# brashmi.net
KiCad netlist of a schematic drawn in EasyEDA
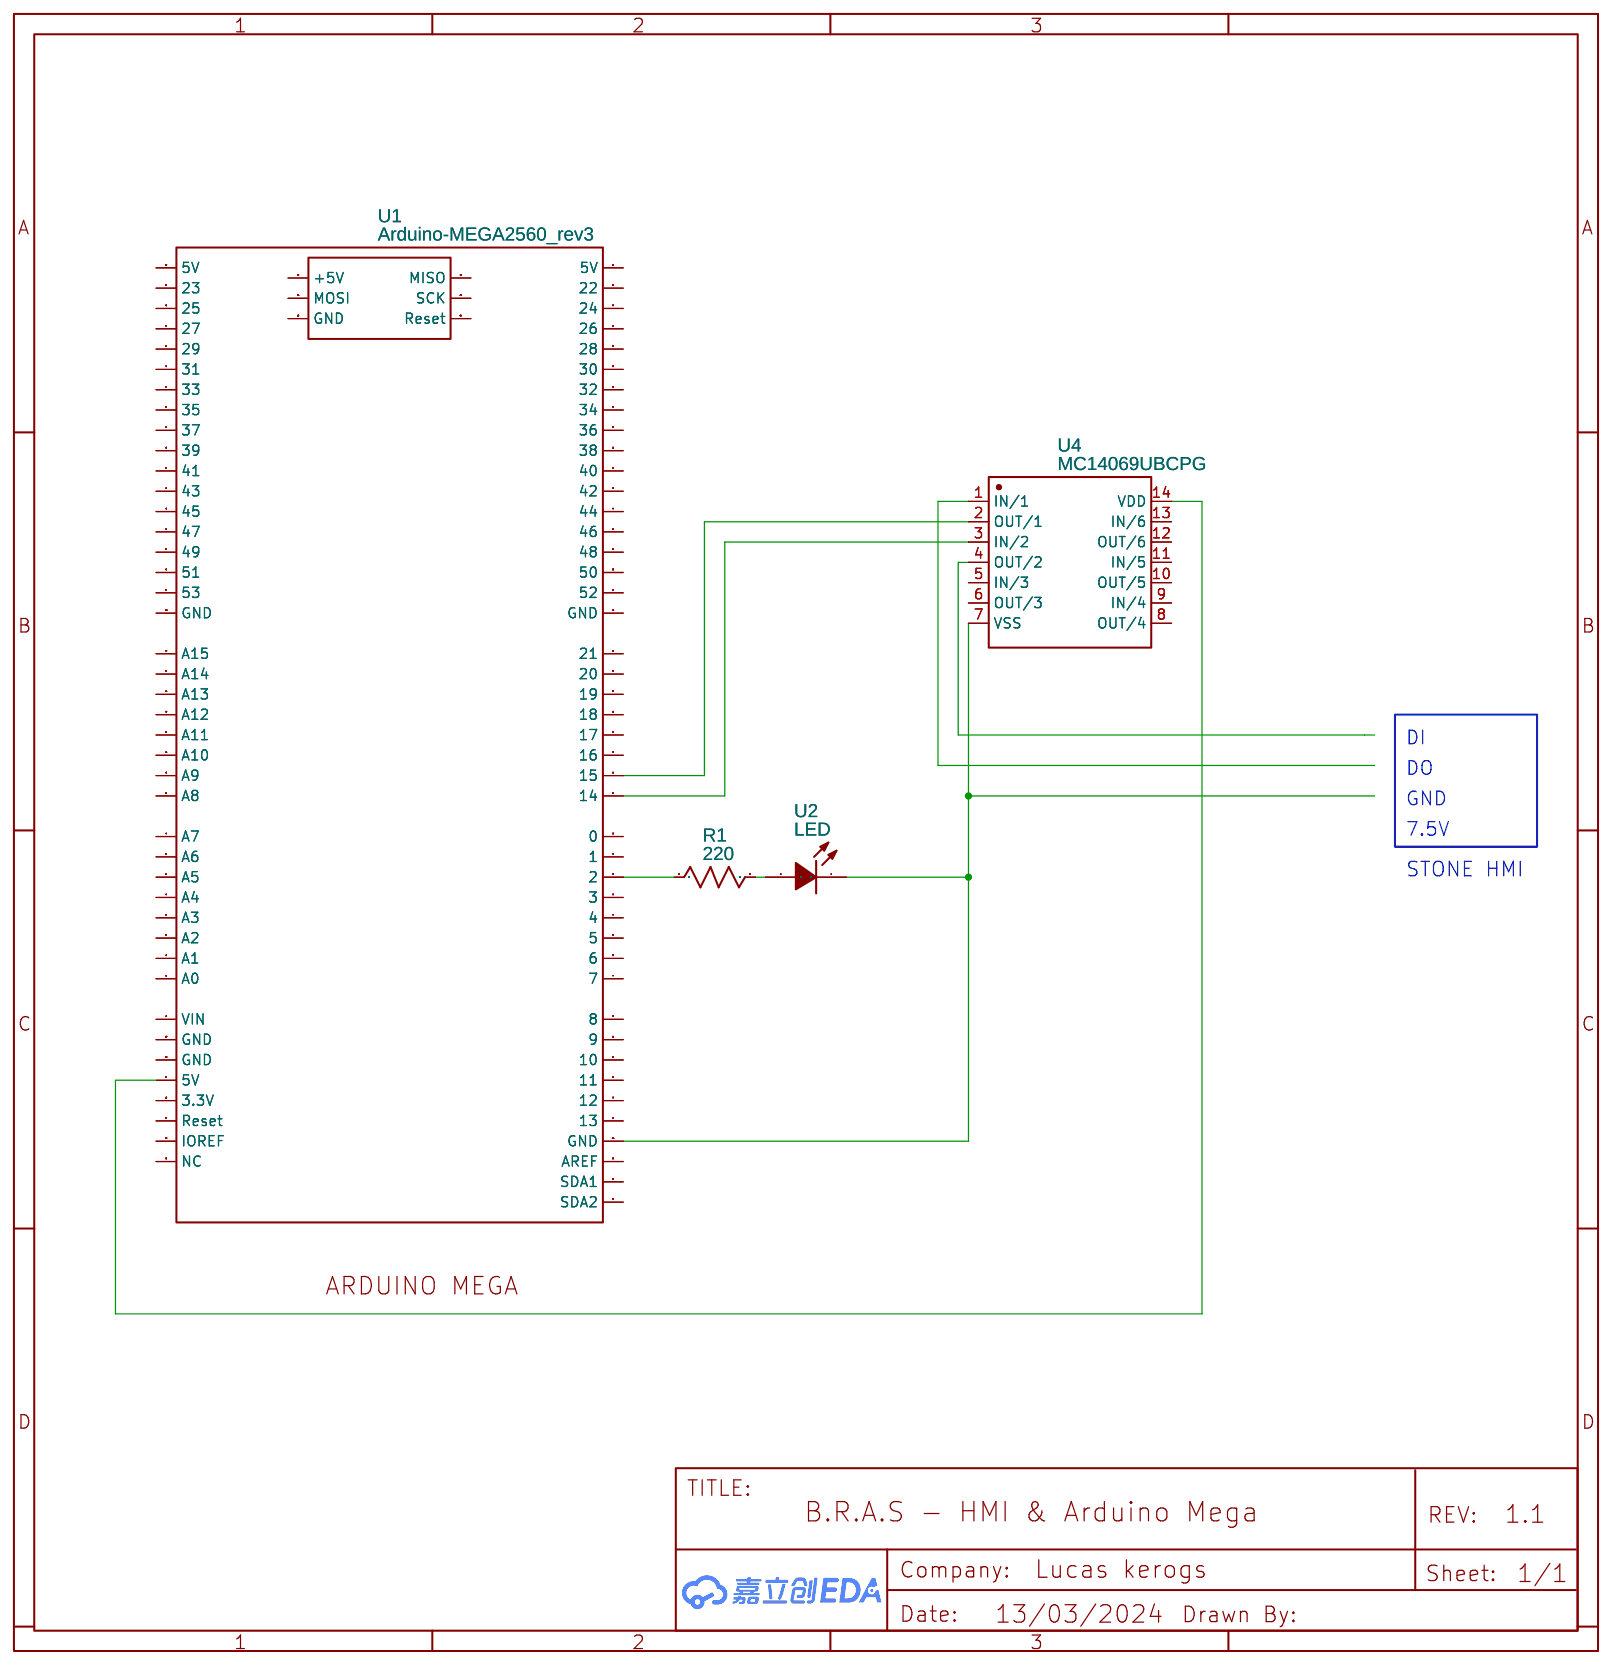
[diagram p0: schematic sheet]

(export (version "E")
  (design (tool "Eeschema 10.0.6"))
  (components
    (comp (ref "R1") (value "220") (libsource (lib "") (part "R_0603_US")))
    (comp (ref "U1") (value "Arduino-MEGA2560_rev3") (libsource (lib "") (part "Arduino-MEGA2560_rev3")))
    (comp (ref "U2")
      (value "LED")
      (fields (field (name "Manufacturer Part") "720-LCGH9RNMXNX1"))
      (libsource (lib "") (part "720-LCGH9RNMXNX1"))
    )
    (comp (ref "U4") (value "MC14069UBCPG") (libsource (lib "") (part "MC14069UBCPG")))
  )
  (nets
    (net (code "1") (name "Net-(R1-Pad1)") (class "Default")
      (node (ref "R1") (pin "1") (pinfunction "1_1") (pintype "unspecified"))
      (node (ref "U1") (pin "2") (pinfunction "2_2") (pintype "unspecified"))
    )
    (net (code "2") (name "Net-(U2-A)") (class "Default")
      (node (ref "R1") (pin "2") (pinfunction "2_2") (pintype "unspecified"))
      (node (ref "U2") (pin "2") (pinfunction "A_2") (pintype "unspecified"))
    )
    (net (code "3") (name "Net-(U2-K)") (class "Default")
      (node (ref "U1") (pin "GND.....") (pinfunction "GND_GND.....") (pintype "unspecified"))
      (node (ref "U2") (pin "1") (pinfunction "K_1") (pintype "unspecified"))
      (node (ref "U4") (pin "7") (pinfunction "VSS_7") (pintype "unspecified"))
    )
    (net (code "4") (name "Net-(U4-IN{slash}2)") (class "Default")
      (node (ref "U1") (pin "14") (pinfunction "14_14") (pintype "unspecified"))
      (node (ref "U4") (pin "3") (pinfunction "IN/2_3") (pintype "unspecified"))
    )
    (net (code "5") (name "Net-(U4-OUT{slash}1)") (class "Default")
      (node (ref "U1") (pin "15") (pinfunction "15_15") (pintype "unspecified"))
      (node (ref "U4") (pin "2") (pinfunction "OUT/1_2") (pintype "unspecified"))
    )
    (net (code "6") (name "Net-(U4-VDD)") (class "Default")
      (node (ref "U1") (pin "5V") (pinfunction "5V_5V") (pintype "unspecified"))
      (node (ref "U4") (pin "14") (pinfunction "VDD_14") (pintype "unspecified"))
    )
    (net (code "7") (name "unconnected-(U1-+5V-Pad+5V_)") (class "Default")
      (node (ref "U1") (pin "+5V_") (pinfunction "+5V_+5V_") (pintype "unspecified"))
    )
    (net (code "8") (name "unconnected-(U1-5V-Pad5V.)") (class "Default")
      (node (ref "U1") (pin "5V.") (pinfunction "5V_5V.") (pintype "unspecified"))
    )
    (net (code "9") (name "unconnected-(U1-5V-Pad5V..)") (class "Default")
      (node (ref "U1") (pin "5V..") (pinfunction "5V_5V..") (pintype "unspecified"))
    )
    (net (code "10") (name "unconnected-(U1-GND-PadGND.)") (class "Default")
      (node (ref "U1") (pin "GND.") (pinfunction "GND_GND.") (pintype "unspecified"))
    )
    (net (code "11") (name "unconnected-(U1-GND-PadGND..)") (class "Default")
      (node (ref "U1") (pin "GND..") (pinfunction "GND_GND..") (pintype "unspecified"))
    )
    (net (code "12") (name "unconnected-(U1-GND-PadGND...)") (class "Default")
      (node (ref "U1") (pin "GND...") (pinfunction "GND_GND...") (pintype "unspecified"))
    )
    (net (code "13") (name "unconnected-(U1-GND-PadGND....)") (class "Default")
      (node (ref "U1") (pin "GND....") (pinfunction "GND_GND....") (pintype "unspecified"))
    )
    (net (code "14") (name "unconnected-(U1-GND-PadGND_)") (class "Default")
      (node (ref "U1") (pin "GND_") (pinfunction "GND_GND_") (pintype "unspecified"))
    )
    (net (code "15") (name "unconnected-(U1-NC-Pad87)") (class "Default")
      (node (ref "U1") (pin "87") (pinfunction "NC_87") (pintype "unspecified"))
    )
    (net (code "16") (name "unconnected-(U1-Pad0)") (class "Default")
      (node (ref "U1") (pin "0") (pinfunction "0_0") (pintype "unspecified"))
    )
    (net (code "17") (name "unconnected-(U1-Pad1)") (class "Default")
      (node (ref "U1") (pin "1") (pinfunction "1_1") (pintype "unspecified"))
    )
    (net (code "18") (name "unconnected-(U1-Pad3)") (class "Default")
      (node (ref "U1") (pin "3") (pinfunction "3_3") (pintype "unspecified"))
    )
    (net (code "19") (name "unconnected-(U1-Pad3.3V)") (class "Default")
      (node (ref "U1") (pin "3.3V") (pinfunction "3.3V_3.3V") (pintype "unspecified"))
    )
    (net (code "20") (name "unconnected-(U1-Pad4)") (class "Default")
      (node (ref "U1") (pin "4") (pinfunction "4_4") (pintype "unspecified"))
    )
    (net (code "21") (name "unconnected-(U1-Pad5)") (class "Default")
      (node (ref "U1") (pin "5") (pinfunction "5_5") (pintype "unspecified"))
    )
    (net (code "22") (name "unconnected-(U1-Pad6)") (class "Default")
      (node (ref "U1") (pin "6") (pinfunction "6_6") (pintype "unspecified"))
    )
    (net (code "23") (name "unconnected-(U1-Pad7)") (class "Default")
      (node (ref "U1") (pin "7") (pinfunction "7_7") (pintype "unspecified"))
    )
    (net (code "24") (name "unconnected-(U1-Pad8)") (class "Default")
      (node (ref "U1") (pin "8") (pinfunction "8_8") (pintype "unspecified"))
    )
    (net (code "25") (name "unconnected-(U1-Pad9)") (class "Default")
      (node (ref "U1") (pin "9") (pinfunction "9_9") (pintype "unspecified"))
    )
    (net (code "26") (name "unconnected-(U1-Pad10)") (class "Default")
      (node (ref "U1") (pin "10") (pinfunction "10_10") (pintype "unspecified"))
    )
    (net (code "27") (name "unconnected-(U1-Pad11)") (class "Default")
      (node (ref "U1") (pin "11") (pinfunction "11_11") (pintype "unspecified"))
    )
    (net (code "28") (name "unconnected-(U1-Pad12)") (class "Default")
      (node (ref "U1") (pin "12") (pinfunction "12_12") (pintype "unspecified"))
    )
    (net (code "29") (name "unconnected-(U1-Pad13)") (class "Default")
      (node (ref "U1") (pin "13") (pinfunction "13_13") (pintype "unspecified"))
    )
    (net (code "30") (name "unconnected-(U1-Pad16)") (class "Default")
      (node (ref "U1") (pin "16") (pinfunction "16_16") (pintype "unspecified"))
    )
    (net (code "31") (name "unconnected-(U1-Pad17)") (class "Default")
      (node (ref "U1") (pin "17") (pinfunction "17_17") (pintype "unspecified"))
    )
    (net (code "32") (name "unconnected-(U1-Pad18)") (class "Default")
      (node (ref "U1") (pin "18") (pinfunction "18_18") (pintype "unspecified"))
    )
    (net (code "33") (name "unconnected-(U1-Pad19)") (class "Default")
      (node (ref "U1") (pin "19") (pinfunction "19_19") (pintype "unspecified"))
    )
    (net (code "34") (name "unconnected-(U1-Pad20)") (class "Default")
      (node (ref "U1") (pin "20") (pinfunction "20_20") (pintype "unspecified"))
    )
    (net (code "35") (name "unconnected-(U1-Pad21)") (class "Default")
      (node (ref "U1") (pin "21") (pinfunction "21_21") (pintype "unspecified"))
    )
    (net (code "36") (name "unconnected-(U1-Pad22)") (class "Default")
      (node (ref "U1") (pin "22") (pinfunction "22_22") (pintype "unspecified"))
    )
    (net (code "37") (name "unconnected-(U1-Pad23)") (class "Default")
      (node (ref "U1") (pin "23") (pinfunction "23_23") (pintype "unspecified"))
    )
    (net (code "38") (name "unconnected-(U1-Pad24)") (class "Default")
      (node (ref "U1") (pin "24") (pinfunction "24_24") (pintype "unspecified"))
    )
    (net (code "39") (name "unconnected-(U1-Pad25)") (class "Default")
      (node (ref "U1") (pin "25") (pinfunction "25_25") (pintype "unspecified"))
    )
    (net (code "40") (name "unconnected-(U1-Pad26)") (class "Default")
      (node (ref "U1") (pin "26") (pinfunction "26_26") (pintype "unspecified"))
    )
    (net (code "41") (name "unconnected-(U1-Pad27)") (class "Default")
      (node (ref "U1") (pin "27") (pinfunction "27_27") (pintype "unspecified"))
    )
    (net (code "42") (name "unconnected-(U1-Pad28)") (class "Default")
      (node (ref "U1") (pin "28") (pinfunction "28_28") (pintype "unspecified"))
    )
    (net (code "43") (name "unconnected-(U1-Pad29)") (class "Default")
      (node (ref "U1") (pin "29") (pinfunction "29_29") (pintype "unspecified"))
    )
    (net (code "44") (name "unconnected-(U1-Pad30)") (class "Default")
      (node (ref "U1") (pin "30") (pinfunction "30_30") (pintype "unspecified"))
    )
    (net (code "45") (name "unconnected-(U1-Pad31)") (class "Default")
      (node (ref "U1") (pin "31") (pinfunction "31_31") (pintype "unspecified"))
    )
    (net (code "46") (name "unconnected-(U1-Pad32)") (class "Default")
      (node (ref "U1") (pin "32") (pinfunction "32_32") (pintype "unspecified"))
    )
    (net (code "47") (name "unconnected-(U1-Pad33)") (class "Default")
      (node (ref "U1") (pin "33") (pinfunction "33_33") (pintype "unspecified"))
    )
    (net (code "48") (name "unconnected-(U1-Pad34)") (class "Default")
      (node (ref "U1") (pin "34") (pinfunction "34_34") (pintype "unspecified"))
    )
    (net (code "49") (name "unconnected-(U1-Pad35)") (class "Default")
      (node (ref "U1") (pin "35") (pinfunction "35_35") (pintype "unspecified"))
    )
    (net (code "50") (name "unconnected-(U1-Pad36)") (class "Default")
      (node (ref "U1") (pin "36") (pinfunction "36_36") (pintype "unspecified"))
    )
    (net (code "51") (name "unconnected-(U1-Pad37)") (class "Default")
      (node (ref "U1") (pin "37") (pinfunction "37_37") (pintype "unspecified"))
    )
    (net (code "52") (name "unconnected-(U1-Pad38)") (class "Default")
      (node (ref "U1") (pin "38") (pinfunction "38_38") (pintype "unspecified"))
    )
    (net (code "53") (name "unconnected-(U1-Pad39)") (class "Default")
      (node (ref "U1") (pin "39") (pinfunction "39_39") (pintype "unspecified"))
    )
    (net (code "54") (name "unconnected-(U1-Pad40)") (class "Default")
      (node (ref "U1") (pin "40") (pinfunction "40_40") (pintype "unspecified"))
    )
    (net (code "55") (name "unconnected-(U1-Pad41)") (class "Default")
      (node (ref "U1") (pin "41") (pinfunction "41_41") (pintype "unspecified"))
    )
    (net (code "56") (name "unconnected-(U1-Pad42)") (class "Default")
      (node (ref "U1") (pin "42") (pinfunction "42_42") (pintype "unspecified"))
    )
    (net (code "57") (name "unconnected-(U1-Pad43)") (class "Default")
      (node (ref "U1") (pin "43") (pinfunction "43_43") (pintype "unspecified"))
    )
    (net (code "58") (name "unconnected-(U1-Pad44)") (class "Default")
      (node (ref "U1") (pin "44") (pinfunction "44_44") (pintype "unspecified"))
    )
    (net (code "59") (name "unconnected-(U1-Pad45)") (class "Default")
      (node (ref "U1") (pin "45") (pinfunction "45_45") (pintype "unspecified"))
    )
    (net (code "60") (name "unconnected-(U1-Pad46)") (class "Default")
      (node (ref "U1") (pin "46") (pinfunction "46_46") (pintype "unspecified"))
    )
    (net (code "61") (name "unconnected-(U1-Pad47)") (class "Default")
      (node (ref "U1") (pin "47") (pinfunction "47_47") (pintype "unspecified"))
    )
    (net (code "62") (name "unconnected-(U1-Pad48)") (class "Default")
      (node (ref "U1") (pin "48") (pinfunction "48_48") (pintype "unspecified"))
    )
    (net (code "63") (name "unconnected-(U1-Pad49)") (class "Default")
      (node (ref "U1") (pin "49") (pinfunction "49_49") (pintype "unspecified"))
    )
    (net (code "64") (name "unconnected-(U1-Pad50)") (class "Default")
      (node (ref "U1") (pin "50") (pinfunction "50_50") (pintype "unspecified"))
    )
    (net (code "65") (name "unconnected-(U1-Pad51)") (class "Default")
      (node (ref "U1") (pin "51") (pinfunction "51_51") (pintype "unspecified"))
    )
    (net (code "66") (name "unconnected-(U1-Pad52)") (class "Default")
      (node (ref "U1") (pin "52") (pinfunction "52_52") (pintype "unspecified"))
    )
    (net (code "67") (name "unconnected-(U1-Pad53)") (class "Default")
      (node (ref "U1") (pin "53") (pinfunction "53_53") (pintype "unspecified"))
    )
    (net (code "68") (name "unconnected-(U1-PadA0)") (class "Default")
      (node (ref "U1") (pin "A0") (pinfunction "A0_A0") (pintype "unspecified"))
    )
    (net (code "69") (name "unconnected-(U1-PadA1)") (class "Default")
      (node (ref "U1") (pin "A1") (pinfunction "A1_A1") (pintype "unspecified"))
    )
    (net (code "70") (name "unconnected-(U1-PadA2)") (class "Default")
      (node (ref "U1") (pin "A2") (pinfunction "A2_A2") (pintype "unspecified"))
    )
    (net (code "71") (name "unconnected-(U1-PadA3)") (class "Default")
      (node (ref "U1") (pin "A3") (pinfunction "A3_A3") (pintype "unspecified"))
    )
    (net (code "72") (name "unconnected-(U1-PadA4)") (class "Default")
      (node (ref "U1") (pin "A4") (pinfunction "A4_A4") (pintype "unspecified"))
    )
    (net (code "73") (name "unconnected-(U1-PadA5)") (class "Default")
      (node (ref "U1") (pin "A5") (pinfunction "A5_A5") (pintype "unspecified"))
    )
    (net (code "74") (name "unconnected-(U1-PadA6)") (class "Default")
      (node (ref "U1") (pin "A6") (pinfunction "A6_A6") (pintype "unspecified"))
    )
    (net (code "75") (name "unconnected-(U1-PadA7)") (class "Default")
      (node (ref "U1") (pin "A7") (pinfunction "A7_A7") (pintype "unspecified"))
    )
    (net (code "76") (name "unconnected-(U1-PadA8)") (class "Default")
      (node (ref "U1") (pin "A8") (pinfunction "A8_A8") (pintype "unspecified"))
    )
    (net (code "77") (name "unconnected-(U1-PadA9)") (class "Default")
      (node (ref "U1") (pin "A9") (pinfunction "A9_A9") (pintype "unspecified"))
    )
    (net (code "78") (name "unconnected-(U1-PadA10)") (class "Default")
      (node (ref "U1") (pin "A10") (pinfunction "A10_A10") (pintype "unspecified"))
    )
    (net (code "79") (name "unconnected-(U1-PadA11)") (class "Default")
      (node (ref "U1") (pin "A11") (pinfunction "A11_A11") (pintype "unspecified"))
    )
    (net (code "80") (name "unconnected-(U1-PadA12)") (class "Default")
      (node (ref "U1") (pin "A12") (pinfunction "A12_A12") (pintype "unspecified"))
    )
    (net (code "81") (name "unconnected-(U1-PadA13)") (class "Default")
      (node (ref "U1") (pin "A13") (pinfunction "A13_A13") (pintype "unspecified"))
    )
    (net (code "82") (name "unconnected-(U1-PadA14)") (class "Default")
      (node (ref "U1") (pin "A14") (pinfunction "A14_A14") (pintype "unspecified"))
    )
    (net (code "83") (name "unconnected-(U1-PadA15)") (class "Default")
      (node (ref "U1") (pin "A15") (pinfunction "A15_A15") (pintype "unspecified"))
    )
    (net (code "84") (name "unconnected-(U1-PadAREF)") (class "Default")
      (node (ref "U1") (pin "AREF") (pinfunction "AREF_AREF") (pintype "unspecified"))
    )
    (net (code "85") (name "unconnected-(U1-PadIOREF)") (class "Default")
      (node (ref "U1") (pin "IOREF") (pinfunction "IOREF_IOREF") (pintype "unspecified"))
    )
    (net (code "86") (name "unconnected-(U1-PadMISO)") (class "Default")
      (node (ref "U1") (pin "MISO") (pinfunction "MISO_MISO") (pintype "unspecified"))
    )
    (net (code "87") (name "unconnected-(U1-PadMOSI)") (class "Default")
      (node (ref "U1") (pin "MOSI") (pinfunction "MOSI_MOSI") (pintype "unspecified"))
    )
    (net (code "88") (name "unconnected-(U1-PadSCK)") (class "Default")
      (node (ref "U1") (pin "SCK") (pinfunction "SCK_SCK") (pintype "unspecified"))
    )
    (net (code "89") (name "unconnected-(U1-PadSDA1)") (class "Default")
      (node (ref "U1") (pin "SDA1") (pinfunction "SDA1_SDA1") (pintype "unspecified"))
    )
    (net (code "90") (name "unconnected-(U1-PadSDA2)") (class "Default")
      (node (ref "U1") (pin "SDA2") (pinfunction "SDA2_SDA2") (pintype "unspecified"))
    )
    (net (code "91") (name "unconnected-(U1-PadVIN)") (class "Default")
      (node (ref "U1") (pin "VIN") (pinfunction "VIN_VIN") (pintype "unspecified"))
    )
    (net (code "92") (name "unconnected-(U1-Reset-PadRESET_)") (class "Default")
      (node (ref "U1") (pin "RESET_") (pinfunction "Reset_RESET_") (pintype "unspecified"))
    )
    (net (code "93") (name "unconnected-(U1-Reset-PadRST)") (class "Default")
      (node (ref "U1") (pin "RST") (pinfunction "Reset_RST") (pintype "unspecified"))
    )
    (net (code "94") (name "unconnected-(U4-IN{slash}1-Pad1)") (class "Default")
      (node (ref "U4") (pin "1") (pinfunction "IN/1_1") (pintype "unspecified"))
    )
    (net (code "95") (name "unconnected-(U4-IN{slash}3-Pad5)") (class "Default")
      (node (ref "U4") (pin "5") (pinfunction "IN/3_5") (pintype "unspecified"))
    )
    (net (code "96") (name "unconnected-(U4-IN{slash}4-Pad9)") (class "Default")
      (node (ref "U4") (pin "9") (pinfunction "IN/4_9") (pintype "unspecified"))
    )
    (net (code "97") (name "unconnected-(U4-IN{slash}5-Pad11)") (class "Default")
      (node (ref "U4") (pin "11") (pinfunction "IN/5_11") (pintype "unspecified"))
    )
    (net (code "98") (name "unconnected-(U4-IN{slash}6-Pad13)") (class "Default")
      (node (ref "U4") (pin "13") (pinfunction "IN/6_13") (pintype "unspecified"))
    )
    (net (code "99") (name "unconnected-(U4-OUT{slash}2-Pad4)") (class "Default")
      (node (ref "U4") (pin "4") (pinfunction "OUT/2_4") (pintype "unspecified"))
    )
    (net (code "100") (name "unconnected-(U4-OUT{slash}3-Pad6)") (class "Default")
      (node (ref "U4") (pin "6") (pinfunction "OUT/3_6") (pintype "unspecified"))
    )
    (net (code "101") (name "unconnected-(U4-OUT{slash}4-Pad8)") (class "Default")
      (node (ref "U4") (pin "8") (pinfunction "OUT/4_8") (pintype "unspecified"))
    )
    (net (code "102") (name "unconnected-(U4-OUT{slash}5-Pad10)") (class "Default")
      (node (ref "U4") (pin "10") (pinfunction "OUT/5_10") (pintype "unspecified"))
    )
    (net (code "103") (name "unconnected-(U4-OUT{slash}6-Pad12)") (class "Default")
      (node (ref "U4") (pin "12") (pinfunction "OUT/6_12") (pintype "unspecified"))
    )
  )
)
